# Sheet1_-_mos.net
KiCad netlist of a schematic drawn in Altium Designer
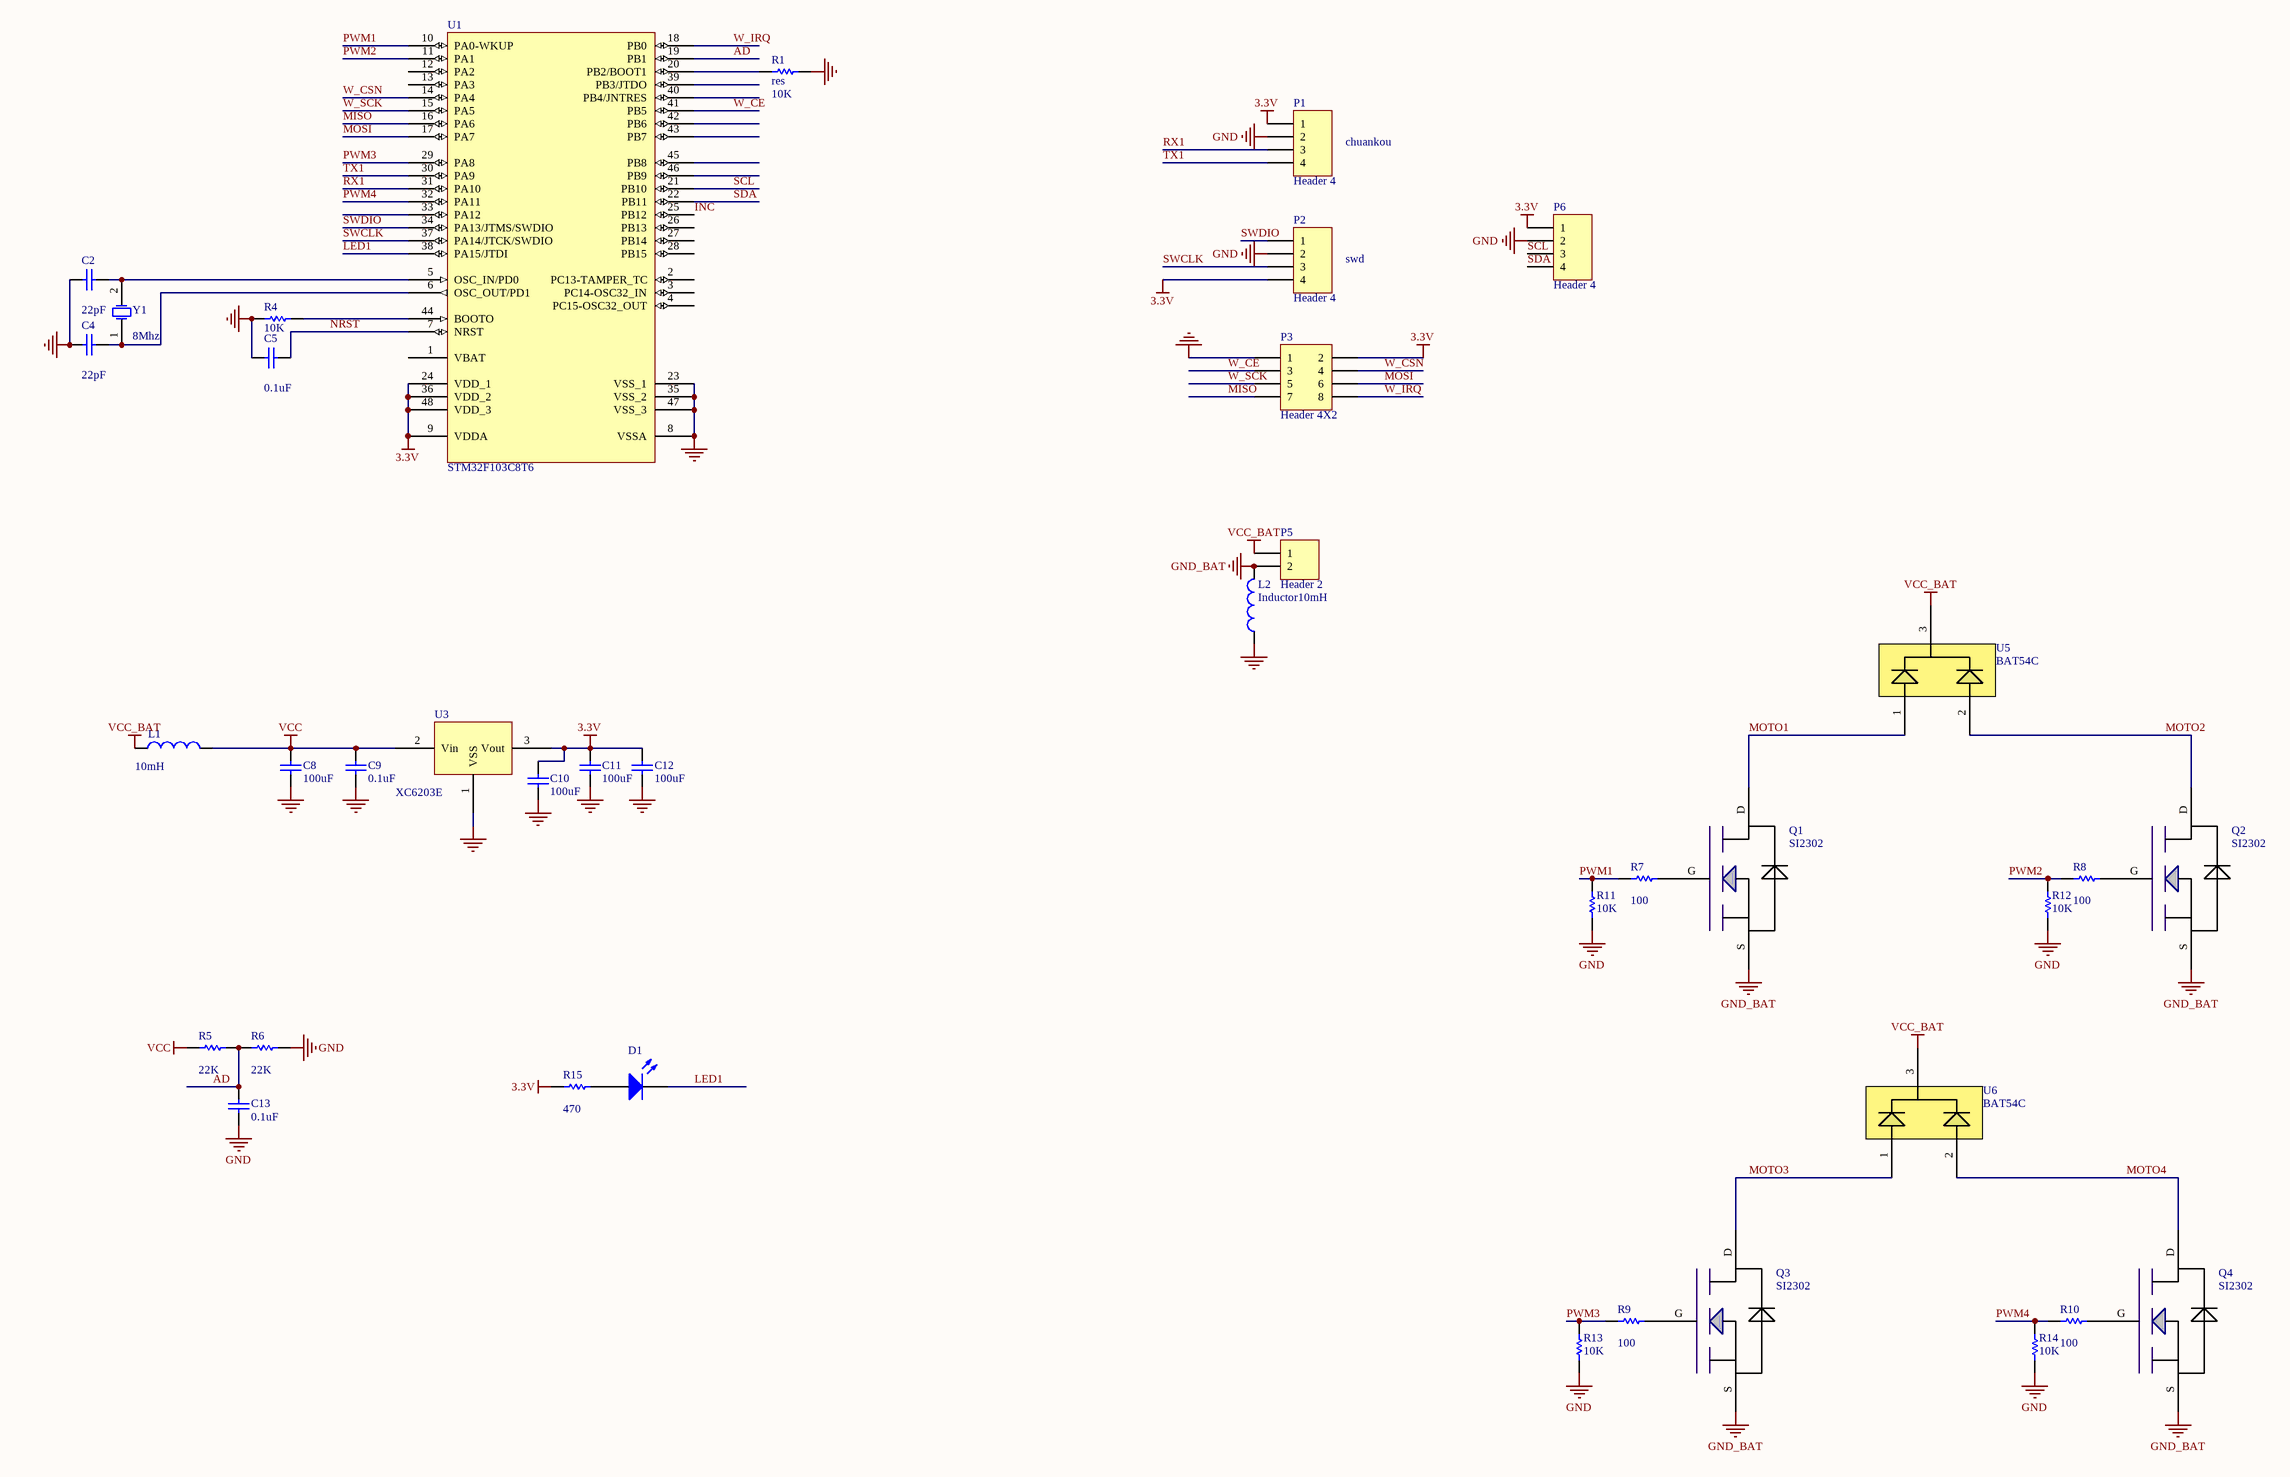
[diagram p0: Sheet1 - 修改mos管.SchDoc]

(export (version "E")
  (design (tool "Eeschema 10.0.6"))
  (components
    (comp (ref "C2")
      (value "22pF")
      (footprint "0603")
      (fields (field (name "Comment") "cap"))
      (libsource (lib "bai") (part "cap"))
    )
    (comp (ref "C4")
      (value "22pF")
      (footprint "0603")
      (fields (field (name "Comment") "cap"))
      (libsource (lib "bai") (part "cap"))
    )
    (comp (ref "C5")
      (value "0.1uF")
      (footprint "0603")
      (fields (field (name "Comment") "cap"))
      (libsource (lib "bai") (part "cap"))
    )
    (comp (ref "C8")
      (value "100uF")
      (footprint "0603")
      (fields (field (name "Comment") "cap"))
      (libsource (lib "bai") (part "cap"))
    )
    (comp (ref "C9")
      (value "0.1uF")
      (footprint "0603")
      (fields (field (name "Comment") "cap"))
      (libsource (lib "bai") (part "cap"))
    )
    (comp (ref "C10")
      (value "100uF")
      (footprint "0603")
      (fields (field (name "Comment") "cap"))
      (libsource (lib "bai") (part "cap"))
    )
    (comp (ref "C11")
      (value "100uF")
      (footprint "0603")
      (fields (field (name "Comment") "cap"))
      (libsource (lib "bai") (part "cap"))
    )
    (comp (ref "C12")
      (value "100uF")
      (footprint "0603")
      (fields (field (name "Comment") "cap"))
      (libsource (lib "bai") (part "cap"))
    )
    (comp (ref "C13")
      (value "0.1uF")
      (footprint "0603")
      (fields (field (name "Comment") "cap"))
      (libsource (lib "bai") (part "cap"))
    )
    (comp (ref "D1")
      (value "LED0")
      (footprint "0805")
      (description "Typical INFRARED GaAs LED")
      (fields (field (name "PUBLISHER") "Altium Limited"))
      (libsource (lib "Miscellaneous Devices") (part "LED0"))
    )
    (comp (ref "L1")
      (value "10mH")
      (footprint "0805")
      (fields (field (name "Comment") "Inductor"))
      (libsource (lib "bai") (part "Inductor"))
    )
    (comp (ref "L2") (value "Inductor10mH") (footprint "0805") (libsource (lib "bai") (part "Inductor")))
    (comp (ref "P1")
      (value "Header 4")
      (footprint "HDR1X4")
      (description "Header, 4-Pin")
      (fields (field (name "PUBLISHER") "Altium Limited"))
      (libsource (lib "Miscellaneous Connectors") (part "Header 4"))
    )
    (comp (ref "P2")
      (value "Header 4")
      (footprint "HDR1X4")
      (description "Header, 4-Pin")
      (fields (field (name "PUBLISHER") "Altium Limited"))
      (libsource (lib "Miscellaneous Connectors") (part "Header 4"))
    )
    (comp (ref "P3")
      (value "Header 4X2")
      (footprint "HDR2X4")
      (description "Header, 4-Pin, Dual row")
      (fields (field (name "PUBLISHER") "Altium Limited"))
      (libsource (lib "Miscellaneous Connectors") (part "Header 4X2"))
    )
    (comp (ref "P5")
      (value "Header 2")
      (footprint "HDR1X2")
      (description "Header, 2-Pin")
      (fields (field (name "PUBLISHER") "Altium Limited"))
      (libsource (lib "Miscellaneous Connectors") (part "Header 2"))
    )
    (comp (ref "P6")
      (value "Header 4")
      (footprint "HDR1X4")
      (description "Header, 4-Pin")
      (fields (field (name "PUBLISHER") "Altium Limited"))
      (libsource (lib "Miscellaneous Connectors") (part "Header 4"))
    )
    (comp (ref "Q1") (value "SI2302") (footprint "SOT-23") (libsource (lib "bai") (part "SI2302")))
    (comp (ref "Q2") (value "SI2302") (footprint "SOT-23") (libsource (lib "bai") (part "SI2302")))
    (comp (ref "Q3") (value "SI2302") (footprint "SOT-23") (libsource (lib "bai") (part "SI2302")))
    (comp (ref "Q4") (value "SI2302") (footprint "SOT-23") (libsource (lib "bai") (part "SI2302")))
    (comp (ref "R1")
      (value "res")
      (footprint "0603")
      (fields (field (name "RES") "10K"))
      (libsource (lib "bai") (part "res"))
    )
    (comp (ref "R4")
      (value "res")
      (footprint "0603")
      (fields (field (name "RES") "10K"))
      (libsource (lib "bai") (part "res"))
    )
    (comp (ref "R5")
      (value "res")
      (footprint "0603")
      (fields (field (name "RES") "22K"))
      (libsource (lib "bai") (part "res"))
    )
    (comp (ref "R6")
      (value "res")
      (footprint "0603")
      (fields (field (name "RES") "22K"))
      (libsource (lib "bai") (part "res"))
    )
    (comp (ref "R7")
      (value "res")
      (footprint "0603")
      (fields (field (name "RES") "100"))
      (libsource (lib "bai") (part "res"))
    )
    (comp (ref "R8")
      (value "res")
      (footprint "0603")
      (fields (field (name "RES") "100"))
      (libsource (lib "bai") (part "res"))
    )
    (comp (ref "R9")
      (value "res")
      (footprint "0603")
      (fields (field (name "RES") "100"))
      (libsource (lib "bai") (part "res"))
    )
    (comp (ref "R10")
      (value "res")
      (footprint "0603")
      (fields (field (name "RES") "100"))
      (libsource (lib "bai") (part "res"))
    )
    (comp (ref "R11")
      (value "res")
      (footprint "0603")
      (fields (field (name "RES") "10K"))
      (libsource (lib "bai") (part "res"))
    )
    (comp (ref "R12")
      (value "res")
      (footprint "0603")
      (fields (field (name "RES") "10K"))
      (libsource (lib "bai") (part "res"))
    )
    (comp (ref "R13")
      (value "res")
      (footprint "0603")
      (fields (field (name "RES") "10K"))
      (libsource (lib "bai") (part "res"))
    )
    (comp (ref "R14")
      (value "res")
      (footprint "0603")
      (fields (field (name "RES") "10K"))
      (libsource (lib "bai") (part "res"))
    )
    (comp (ref "R15")
      (value "res")
      (footprint "0603")
      (fields (field (name "RES") "470"))
      (libsource (lib "bai") (part "res"))
    )
    (comp (ref "U1")
      (value "STM32F103C8T6")
      (footprint "LQFP48S")
      (libsource (lib "bai") (part "STM32F103C8T6"))
    )
    (comp (ref "U3") (value "XC6203E") (footprint "SOT-89") (libsource (lib "文哥做的") (part "XC6203")))
    (comp (ref "U5") (value "BAT54C") (footprint "SOT-23") (libsource (lib "bai") (part "BAT54C")))
    (comp (ref "U6") (value "BAT54C") (footprint "SOT-23") (libsource (lib "bai") (part "BAT54C")))
    (comp (ref "Y1")
      (value "5032xtal")
      (footprint "XTAL")
      (fields (field (name "ALTIUM_UNNAMED_1") "8Mhz"))
      (libsource (lib "bai") (part "5032xtal"))
    )
  )
  (nets
    (net (code "1") (name "/AD") (class "Default")
      (node (ref "C13") (pin "2") (pinfunction "2_2") (pintype "passive"))
      (node (ref "R5") (pin "2") (pinfunction "2_2") (pintype "passive"))
      (node (ref "R6") (pin "1") (pinfunction "1_1") (pintype "passive"))
      (node (ref "U1") (pin "19") (pinfunction "PB1_19") (pintype "bidirectional"))
    )
    (net (code "2") (name "/INC") (class "Default")
      (node (ref "U1") (pin "25") (pinfunction "PB12_25") (pintype "bidirectional"))
    )
    (net (code "3") (name "/LED1") (class "Default")
      (node (ref "D1") (pin "2") (pinfunction "K_2") (pintype "passive"))
      (node (ref "U1") (pin "38") (pinfunction "PA15/JTDI_38") (pintype "bidirectional"))
    )
    (net (code "4") (name "/MISO") (class "Default")
      (node (ref "P3") (pin "7") (pinfunction "7_7") (pintype "passive"))
      (node (ref "U1") (pin "16") (pinfunction "PA6_16") (pintype "bidirectional"))
    )
    (net (code "5") (name "/MOSI") (class "Default")
      (node (ref "P3") (pin "6") (pinfunction "6_6") (pintype "passive"))
      (node (ref "U1") (pin "17") (pinfunction "PA7_17") (pintype "bidirectional"))
    )
    (net (code "6") (name "/MOTO1") (class "Default")
      (node (ref "Q1") (pin "D") (pinfunction "3_D") (pintype "passive"))
      (node (ref "U5") (pin "1") (pinfunction "4_1") (pintype "passive"))
    )
    (net (code "7") (name "/MOTO2") (class "Default")
      (node (ref "Q2") (pin "D") (pinfunction "3_D") (pintype "passive"))
      (node (ref "U5") (pin "2") (pinfunction "5_2") (pintype "passive"))
    )
    (net (code "8") (name "/MOTO3") (class "Default")
      (node (ref "Q3") (pin "D") (pinfunction "3_D") (pintype "passive"))
      (node (ref "U6") (pin "1") (pinfunction "4_1") (pintype "passive"))
    )
    (net (code "9") (name "/MOTO4") (class "Default")
      (node (ref "Q4") (pin "D") (pinfunction "3_D") (pintype "passive"))
      (node (ref "U6") (pin "2") (pinfunction "5_2") (pintype "passive"))
    )
    (net (code "10") (name "/NRST") (class "Default")
      (node (ref "C5") (pin "2") (pinfunction "2_2") (pintype "passive"))
      (node (ref "U1") (pin "7") (pinfunction "NRST_7") (pintype "bidirectional"))
    )
    (net (code "11") (name "/PWM1") (class "Default")
      (node (ref "R11") (pin "2") (pinfunction "2_2") (pintype "passive"))
      (node (ref "R7") (pin "1") (pinfunction "1_1") (pintype "passive"))
      (node (ref "U1") (pin "10") (pinfunction "PA0-WKUP_10") (pintype "bidirectional"))
    )
    (net (code "12") (name "/PWM2") (class "Default")
      (node (ref "R12") (pin "2") (pinfunction "2_2") (pintype "passive"))
      (node (ref "R8") (pin "1") (pinfunction "1_1") (pintype "passive"))
      (node (ref "U1") (pin "11") (pinfunction "PA1_11") (pintype "bidirectional"))
    )
    (net (code "13") (name "/PWM3") (class "Default")
      (node (ref "R13") (pin "2") (pinfunction "2_2") (pintype "passive"))
      (node (ref "R9") (pin "1") (pinfunction "1_1") (pintype "passive"))
      (node (ref "U1") (pin "29") (pinfunction "PA8_29") (pintype "bidirectional"))
    )
    (net (code "14") (name "/PWM4") (class "Default")
      (node (ref "R10") (pin "1") (pinfunction "1_1") (pintype "passive"))
      (node (ref "R14") (pin "2") (pinfunction "2_2") (pintype "passive"))
      (node (ref "U1") (pin "32") (pinfunction "PA11_32") (pintype "bidirectional"))
    )
    (net (code "15") (name "/RX1") (class "Default")
      (node (ref "P1") (pin "3") (pinfunction "3_3") (pintype "passive"))
      (node (ref "U1") (pin "31") (pinfunction "PA10_31") (pintype "bidirectional"))
    )
    (net (code "16") (name "/SCL") (class "Default")
      (node (ref "P6") (pin "3") (pinfunction "3_3") (pintype "passive"))
      (node (ref "U1") (pin "21") (pinfunction "PB10_21") (pintype "bidirectional"))
    )
    (net (code "17") (name "/SDA") (class "Default")
      (node (ref "P6") (pin "4") (pinfunction "4_4") (pintype "passive"))
      (node (ref "U1") (pin "22") (pinfunction "PB11_22") (pintype "bidirectional"))
    )
    (net (code "18") (name "/SWCLK") (class "Default")
      (node (ref "P2") (pin "3") (pinfunction "3_3") (pintype "passive"))
      (node (ref "U1") (pin "37") (pinfunction "PA14/JTCK/SWDIO_37") (pintype "bidirectional"))
    )
    (net (code "19") (name "/SWDIO") (class "Default")
      (node (ref "P2") (pin "1") (pinfunction "1_1") (pintype "passive"))
      (node (ref "U1") (pin "34") (pinfunction "PA13/JTMS/SWDIO_34") (pintype "bidirectional"))
    )
    (net (code "20") (name "/TX1") (class "Default")
      (node (ref "P1") (pin "4") (pinfunction "4_4") (pintype "passive"))
      (node (ref "U1") (pin "30") (pinfunction "PA9_30") (pintype "bidirectional"))
    )
    (net (code "21") (name "/W_CE") (class "Default")
      (node (ref "P3") (pin "3") (pinfunction "3_3") (pintype "passive"))
      (node (ref "U1") (pin "41") (pinfunction "PB5_41") (pintype "bidirectional"))
    )
    (net (code "22") (name "/W_CSN") (class "Default")
      (node (ref "P3") (pin "4") (pinfunction "4_4") (pintype "passive"))
      (node (ref "U1") (pin "14") (pinfunction "PA4_14") (pintype "bidirectional"))
    )
    (net (code "23") (name "/W_IRQ") (class "Default")
      (node (ref "P3") (pin "8") (pinfunction "8_8") (pintype "passive"))
      (node (ref "U1") (pin "18") (pinfunction "PB0_18") (pintype "bidirectional"))
    )
    (net (code "24") (name "/W_SCK") (class "Default")
      (node (ref "P3") (pin "5") (pinfunction "5_5") (pintype "passive"))
      (node (ref "U1") (pin "15") (pinfunction "PA5_15") (pintype "bidirectional"))
    )
    (net (code "25") (name "3.3V") (class "Default")
      (node (ref "C10") (pin "2") (pinfunction "2_2") (pintype "passive"))
      (node (ref "C11") (pin "2") (pinfunction "2_2") (pintype "passive"))
      (node (ref "C12") (pin "2") (pinfunction "2_2") (pintype "passive"))
      (node (ref "P1") (pin "1") (pinfunction "1_1") (pintype "passive"))
      (node (ref "P2") (pin "4") (pinfunction "4_4") (pintype "passive"))
      (node (ref "P3") (pin "2") (pinfunction "2_2") (pintype "passive"))
      (node (ref "P6") (pin "1") (pinfunction "1_1") (pintype "passive"))
      (node (ref "R15") (pin "1") (pinfunction "1_1") (pintype "passive"))
      (node (ref "U1") (pin "24") (pinfunction "VDD_1_24") (pintype "passive"))
      (node (ref "U1") (pin "36") (pinfunction "VDD_2_36") (pintype "passive"))
      (node (ref "U1") (pin "48") (pinfunction "VDD_3_48") (pintype "passive"))
      (node (ref "U1") (pin "9") (pinfunction "VDDA_9") (pintype "passive"))
      (node (ref "U3") (pin "3") (pinfunction "Vout_3") (pintype "passive"))
    )
    (net (code "26") (name "GND") (class "Default")
      (node (ref "C10") (pin "1") (pinfunction "1_1") (pintype "passive"))
      (node (ref "C11") (pin "1") (pinfunction "1_1") (pintype "passive"))
      (node (ref "C12") (pin "1") (pinfunction "1_1") (pintype "passive"))
      (node (ref "C13") (pin "1") (pinfunction "1_1") (pintype "passive"))
      (node (ref "C2") (pin "1") (pinfunction "1_1") (pintype "passive"))
      (node (ref "C4") (pin "1") (pinfunction "1_1") (pintype "passive"))
      (node (ref "C5") (pin "1") (pinfunction "1_1") (pintype "passive"))
      (node (ref "C8") (pin "1") (pinfunction "1_1") (pintype "passive"))
      (node (ref "C9") (pin "1") (pinfunction "1_1") (pintype "passive"))
      (node (ref "L2") (pin "1") (pinfunction "1_1") (pintype "passive"))
      (node (ref "P1") (pin "2") (pinfunction "2_2") (pintype "passive"))
      (node (ref "P2") (pin "2") (pinfunction "2_2") (pintype "passive"))
      (node (ref "P3") (pin "1") (pinfunction "1_1") (pintype "passive"))
      (node (ref "P6") (pin "2") (pinfunction "2_2") (pintype "passive"))
      (node (ref "R1") (pin "2") (pinfunction "2_2") (pintype "passive"))
      (node (ref "R11") (pin "1") (pinfunction "1_1") (pintype "passive"))
      (node (ref "R12") (pin "1") (pinfunction "1_1") (pintype "passive"))
      (node (ref "R13") (pin "1") (pinfunction "1_1") (pintype "passive"))
      (node (ref "R14") (pin "1") (pinfunction "1_1") (pintype "passive"))
      (node (ref "R4") (pin "1") (pinfunction "1_1") (pintype "passive"))
      (node (ref "R6") (pin "2") (pinfunction "2_2") (pintype "passive"))
      (node (ref "U1") (pin "23") (pinfunction "VSS_1_23") (pintype "passive"))
      (node (ref "U1") (pin "35") (pinfunction "VSS_2_35") (pintype "passive"))
      (node (ref "U1") (pin "47") (pinfunction "VSS_3_47") (pintype "passive"))
      (node (ref "U1") (pin "8") (pinfunction "VSSA_8") (pintype "passive"))
      (node (ref "U3") (pin "1") (pinfunction "VSS_1") (pintype "passive"))
    )
    (net (code "27") (name "GND_BAT") (class "Default")
      (node (ref "L2") (pin "2") (pinfunction "2_2") (pintype "passive"))
      (node (ref "P5") (pin "2") (pinfunction "2_2") (pintype "passive"))
      (node (ref "Q1") (pin "S") (pinfunction "2_S") (pintype "passive"))
      (node (ref "Q2") (pin "S") (pinfunction "2_S") (pintype "passive"))
      (node (ref "Q3") (pin "S") (pinfunction "2_S") (pintype "passive"))
      (node (ref "Q4") (pin "S") (pinfunction "2_S") (pintype "passive"))
    )
    (net (code "28") (name "Net-(D1-A)") (class "Default")
      (node (ref "D1") (pin "1") (pinfunction "A_1") (pintype "passive"))
      (node (ref "R15") (pin "2") (pinfunction "2_2") (pintype "passive"))
    )
    (net (code "29") (name "Net-(Q1-PadG)") (class "Default")
      (node (ref "Q1") (pin "G") (pinfunction "G_G") (pintype "passive"))
      (node (ref "R7") (pin "2") (pinfunction "2_2") (pintype "passive"))
    )
    (net (code "30") (name "Net-(Q2-PadG)") (class "Default")
      (node (ref "Q2") (pin "G") (pinfunction "G_G") (pintype "passive"))
      (node (ref "R8") (pin "2") (pinfunction "2_2") (pintype "passive"))
    )
    (net (code "31") (name "Net-(Q3-PadG)") (class "Default")
      (node (ref "Q3") (pin "G") (pinfunction "G_G") (pintype "passive"))
      (node (ref "R9") (pin "2") (pinfunction "2_2") (pintype "passive"))
    )
    (net (code "32") (name "Net-(Q4-PadG)") (class "Default")
      (node (ref "Q4") (pin "G") (pinfunction "G_G") (pintype "passive"))
      (node (ref "R10") (pin "2") (pinfunction "2_2") (pintype "passive"))
    )
    (net (code "33") (name "Net-(U1-BOOTO)") (class "Default")
      (node (ref "R4") (pin "2") (pinfunction "2_2") (pintype "passive"))
      (node (ref "U1") (pin "44") (pinfunction "BOOTO_44") (pintype "input"))
    )
    (net (code "34") (name "Net-(U1-OSC_IN{slash}PD0)") (class "Default")
      (node (ref "C2") (pin "2") (pinfunction "2_2") (pintype "passive"))
      (node (ref "U1") (pin "5") (pinfunction "OSC_IN/PD0_5") (pintype "input"))
      (node (ref "Y1") (pin "2") (pinfunction "OSC2_2") (pintype "passive"))
    )
    (net (code "35") (name "Net-(U1-OSC_OUT{slash}PD1)") (class "Default")
      (node (ref "C4") (pin "2") (pinfunction "2_2") (pintype "passive"))
      (node (ref "U1") (pin "6") (pinfunction "OSC_OUT/PD1_6") (pintype "output"))
      (node (ref "Y1") (pin "1") (pinfunction "OSC1_1") (pintype "passive"))
    )
    (net (code "36") (name "Net-(U1-PB2{slash}BOOT1)") (class "Default")
      (node (ref "R1") (pin "1") (pinfunction "1_1") (pintype "passive"))
      (node (ref "U1") (pin "20") (pinfunction "PB2/BOOT1_20") (pintype "bidirectional"))
    )
    (net (code "37") (name "VCC") (class "Default")
      (node (ref "C8") (pin "2") (pinfunction "2_2") (pintype "passive"))
      (node (ref "C9") (pin "2") (pinfunction "2_2") (pintype "passive"))
      (node (ref "L1") (pin "2") (pinfunction "2_2") (pintype "passive"))
      (node (ref "R5") (pin "1") (pinfunction "1_1") (pintype "passive"))
      (node (ref "U3") (pin "2") (pinfunction "Vin_2") (pintype "passive"))
    )
    (net (code "38") (name "VCC_BAT") (class "Default")
      (node (ref "L1") (pin "1") (pinfunction "1_1") (pintype "passive"))
      (node (ref "P5") (pin "1") (pinfunction "1_1") (pintype "passive"))
      (node (ref "U5") (pin "3") (pinfunction "0_3") (pintype "passive"))
      (node (ref "U6") (pin "3") (pinfunction "0_3") (pintype "passive"))
    )
    (net (code "39") (name "unconnected-(U1-PA2-Pad12)") (class "Default")
      (node (ref "U1") (pin "12") (pinfunction "PA2_12") (pintype "bidirectional"))
    )
    (net (code "40") (name "unconnected-(U1-PA3-Pad13)") (class "Default")
      (node (ref "U1") (pin "13") (pinfunction "PA3_13") (pintype "bidirectional"))
    )
    (net (code "41") (name "unconnected-(U1-PA12-Pad33)") (class "Default")
      (node (ref "U1") (pin "33") (pinfunction "PA12_33") (pintype "bidirectional"))
    )
    (net (code "42") (name "unconnected-(U1-PB3{slash}JTDO-Pad39)") (class "Default")
      (node (ref "U1") (pin "39") (pinfunction "PB3/JTDO_39") (pintype "bidirectional"))
    )
    (net (code "43") (name "unconnected-(U1-PB4{slash}JNTRES-Pad40)") (class "Default")
      (node (ref "U1") (pin "40") (pinfunction "PB4/JNTRES_40") (pintype "bidirectional"))
    )
    (net (code "44") (name "unconnected-(U1-PB6-Pad42)") (class "Default")
      (node (ref "U1") (pin "42") (pinfunction "PB6_42") (pintype "bidirectional"))
    )
    (net (code "45") (name "unconnected-(U1-PB7-Pad43)") (class "Default")
      (node (ref "U1") (pin "43") (pinfunction "PB7_43") (pintype "bidirectional"))
    )
    (net (code "46") (name "unconnected-(U1-PB8-Pad45)") (class "Default")
      (node (ref "U1") (pin "45") (pinfunction "PB8_45") (pintype "bidirectional"))
    )
    (net (code "47") (name "unconnected-(U1-PB9-Pad46)") (class "Default")
      (node (ref "U1") (pin "46") (pinfunction "PB9_46") (pintype "bidirectional"))
    )
    (net (code "48") (name "unconnected-(U1-PB13-Pad26)") (class "Default")
      (node (ref "U1") (pin "26") (pinfunction "PB13_26") (pintype "bidirectional"))
    )
    (net (code "49") (name "unconnected-(U1-PB14-Pad27)") (class "Default")
      (node (ref "U1") (pin "27") (pinfunction "PB14_27") (pintype "bidirectional"))
    )
    (net (code "50") (name "unconnected-(U1-PB15-Pad28)") (class "Default")
      (node (ref "U1") (pin "28") (pinfunction "PB15_28") (pintype "bidirectional"))
    )
    (net (code "51") (name "unconnected-(U1-PC13-TAMPER_TC-Pad2)") (class "Default")
      (node (ref "U1") (pin "2") (pinfunction "PC13-TAMPER_TC_2") (pintype "bidirectional"))
    )
    (net (code "52") (name "unconnected-(U1-PC14-OSC32_IN-Pad3)") (class "Default")
      (node (ref "U1") (pin "3") (pinfunction "PC14-OSC32_IN_3") (pintype "bidirectional"))
    )
    (net (code "53") (name "unconnected-(U1-PC15-OSC32_OUT-Pad4)") (class "Default")
      (node (ref "U1") (pin "4") (pinfunction "PC15-OSC32_OUT_4") (pintype "bidirectional"))
    )
    (net (code "54") (name "unconnected-(U1-VBAT-Pad1)") (class "Default")
      (node (ref "U1") (pin "1") (pinfunction "VBAT_1") (pintype "passive"))
    )
  )
)
